# FPGA_E.net
KiCad netlist of a schematic drawn in Altium Designer
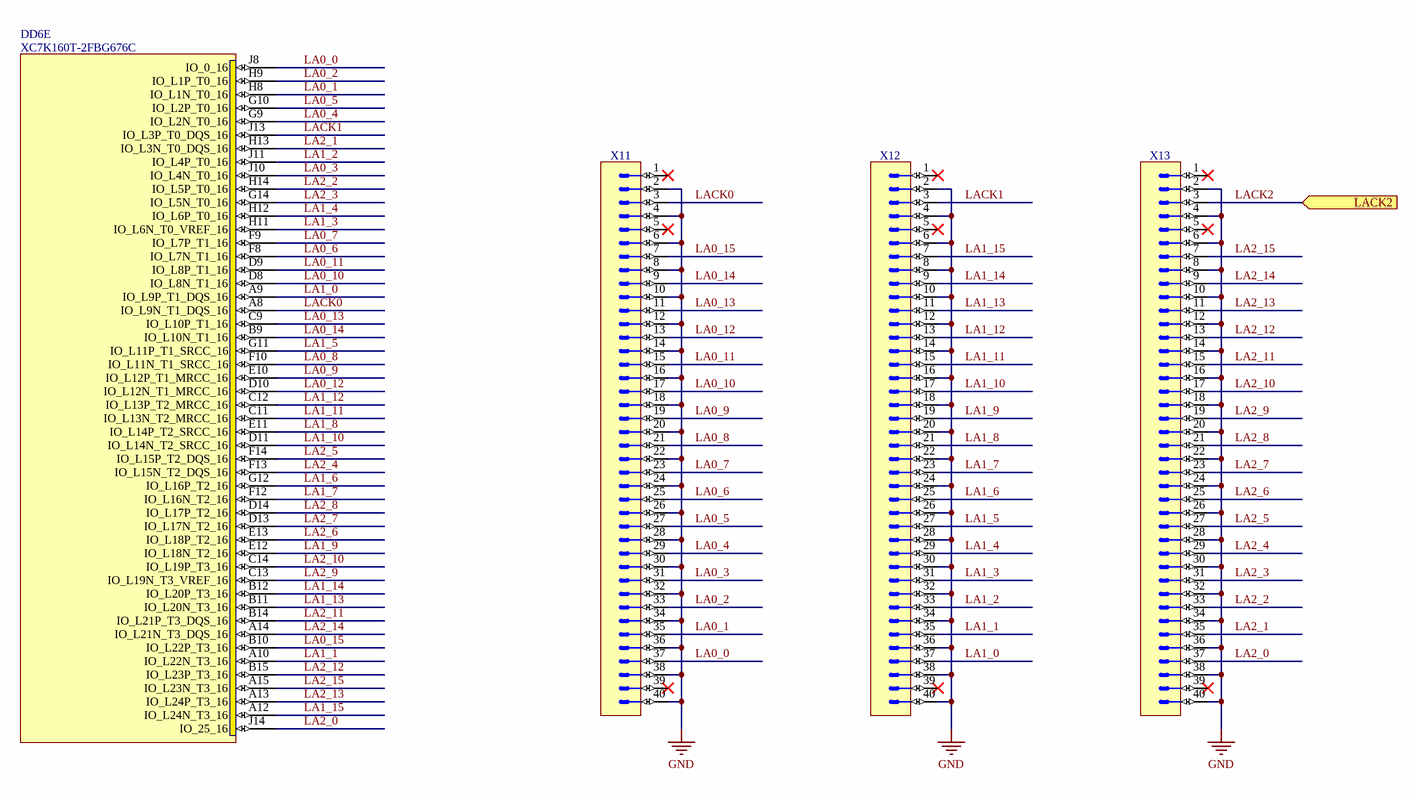
[diagram p0: FPGA_E.SchDoc]

(export (version "E")
  (design (tool "Eeschema 10.0.6"))
  (components
    (comp (ref "DD6")
      (value "XC7K160T-2FBG676C")
      (footprint "BGA676C100P26X26_2700X2700X254")
      (description "KINTEX-7, FPGA, 676-Ball BGA, Pb-Free")
      (fields (field (name "MANUFACTURER") "XILINX") (field (name "AUTHOR") "CERN DEM BC"))
      (libsource (lib "ICs And Semiconductors") (part "XC7K160T-xFBG676"))
    )
    (comp (ref "X11")
      (value "~")
      (footprint "CONNFLY_DS1013-40SSIB1-B-0")
      (description "Connector 40 Male")
      (fields
        (field (name "PART NUMBER") "CONNFLY_DS1013-40SSIB1-B-0")
        (field (name "MANUFACTURER") "CONNFLY")
        (field (name "AUTHOR") "CERN DEM HF")
      )
      (libsource (lib "Connectors") (part "Connector 40 Male"))
    )
    (comp (ref "X12")
      (value "~")
      (footprint "CONNFLY_DS1013-40SSIB1-B-0")
      (description "Connector 40 Male")
      (fields
        (field (name "PART NUMBER") "CONNFLY_DS1013-40SSIB1-B-0")
        (field (name "MANUFACTURER") "CONNFLY")
        (field (name "AUTHOR") "CERN DEM HF")
      )
      (libsource (lib "Connectors") (part "Connector 40 Male"))
    )
    (comp (ref "X13")
      (value "~")
      (footprint "CONNFLY_DS1013-40SSIB1-B-0")
      (description "Connector 40 Male")
      (fields
        (field (name "PART NUMBER") "CONNFLY_DS1013-40SSIB1-B-0")
        (field (name "MANUFACTURER") "CONNFLY")
        (field (name "AUTHOR") "CERN DEM HF")
      )
      (libsource (lib "Connectors") (part "Connector 40 Male"))
    )
  )
  (nets
    (net (code "1") (name "/LA0_0") (class "Default")
      (node (ref "DD6") (pin "J8") (pinfunction "IO_0_16_J8") (pintype "bidirectional"))
      (node (ref "X11") (pin "37") (pinfunction "37_37") (pintype "bidirectional"))
    )
    (net (code "2") (name "/LA0_1") (class "Default")
      (node (ref "DD6") (pin "H8") (pinfunction "IO_L1N_T0_16_H8") (pintype "bidirectional"))
      (node (ref "X11") (pin "35") (pinfunction "35_35") (pintype "bidirectional"))
    )
    (net (code "3") (name "/LA0_2") (class "Default")
      (node (ref "DD6") (pin "H9") (pinfunction "IO_L1P_T0_16_H9") (pintype "bidirectional"))
      (node (ref "X11") (pin "33") (pinfunction "33_33") (pintype "bidirectional"))
    )
    (net (code "4") (name "/LA0_3") (class "Default")
      (node (ref "DD6") (pin "J10") (pinfunction "IO_L4N_T0_16_J10") (pintype "bidirectional"))
      (node (ref "X11") (pin "31") (pinfunction "31_31") (pintype "bidirectional"))
    )
    (net (code "5") (name "/LA0_4") (class "Default")
      (node (ref "DD6") (pin "G9") (pinfunction "IO_L2N_T0_16_G9") (pintype "bidirectional"))
      (node (ref "X11") (pin "29") (pinfunction "29_29") (pintype "bidirectional"))
    )
    (net (code "6") (name "/LA0_5") (class "Default")
      (node (ref "DD6") (pin "G10") (pinfunction "IO_L2P_T0_16_G10") (pintype "bidirectional"))
      (node (ref "X11") (pin "27") (pinfunction "27_27") (pintype "bidirectional"))
    )
    (net (code "7") (name "/LA0_6") (class "Default")
      (node (ref "DD6") (pin "F8") (pinfunction "IO_L7N_T1_16_F8") (pintype "bidirectional"))
      (node (ref "X11") (pin "25") (pinfunction "25_25") (pintype "bidirectional"))
    )
    (net (code "8") (name "/LA0_7") (class "Default")
      (node (ref "DD6") (pin "F9") (pinfunction "IO_L7P_T1_16_F9") (pintype "bidirectional"))
      (node (ref "X11") (pin "23") (pinfunction "23_23") (pintype "bidirectional"))
    )
    (net (code "9") (name "/LA0_8") (class "Default")
      (node (ref "DD6") (pin "F10") (pinfunction "IO_L11N_T1_SRCC_16_F10") (pintype "bidirectional"))
      (node (ref "X11") (pin "21") (pinfunction "21_21") (pintype "bidirectional"))
    )
    (net (code "10") (name "/LA0_9") (class "Default")
      (node (ref "DD6") (pin "E10") (pinfunction "IO_L12P_T1_MRCC_16_E10") (pintype "bidirectional"))
      (node (ref "X11") (pin "19") (pinfunction "19_19") (pintype "bidirectional"))
    )
    (net (code "11") (name "/LA0_10") (class "Default")
      (node (ref "DD6") (pin "D8") (pinfunction "IO_L8N_T1_16_D8") (pintype "bidirectional"))
      (node (ref "X11") (pin "17") (pinfunction "17_17") (pintype "bidirectional"))
    )
    (net (code "12") (name "/LA0_11") (class "Default")
      (node (ref "DD6") (pin "D9") (pinfunction "IO_L8P_T1_16_D9") (pintype "bidirectional"))
      (node (ref "X11") (pin "15") (pinfunction "15_15") (pintype "bidirectional"))
    )
    (net (code "13") (name "/LA0_12") (class "Default")
      (node (ref "DD6") (pin "D10") (pinfunction "IO_L12N_T1_MRCC_16_D10") (pintype "bidirectional"))
      (node (ref "X11") (pin "13") (pinfunction "13_13") (pintype "bidirectional"))
    )
    (net (code "14") (name "/LA0_13") (class "Default")
      (node (ref "DD6") (pin "C9") (pinfunction "IO_L10P_T1_16_C9") (pintype "bidirectional"))
      (node (ref "X11") (pin "11") (pinfunction "11_11") (pintype "bidirectional"))
    )
    (net (code "15") (name "/LA0_14") (class "Default")
      (node (ref "DD6") (pin "B9") (pinfunction "IO_L10N_T1_16_B9") (pintype "bidirectional"))
      (node (ref "X11") (pin "9") (pinfunction "9_9") (pintype "bidirectional"))
    )
    (net (code "16") (name "/LA0_15") (class "Default")
      (node (ref "DD6") (pin "B10") (pinfunction "IO_L22P_T3_16_B10") (pintype "bidirectional"))
      (node (ref "X11") (pin "7") (pinfunction "7_7") (pintype "bidirectional"))
    )
    (net (code "17") (name "/LA1_0") (class "Default")
      (node (ref "DD6") (pin "A9") (pinfunction "IO_L9P_T1_DQS_16_A9") (pintype "bidirectional"))
      (node (ref "X12") (pin "37") (pinfunction "37_37") (pintype "bidirectional"))
    )
    (net (code "18") (name "/LA1_1") (class "Default")
      (node (ref "DD6") (pin "A10") (pinfunction "IO_L22N_T3_16_A10") (pintype "bidirectional"))
      (node (ref "X12") (pin "35") (pinfunction "35_35") (pintype "bidirectional"))
    )
    (net (code "19") (name "/LA1_2") (class "Default")
      (node (ref "DD6") (pin "J11") (pinfunction "IO_L4P_T0_16_J11") (pintype "bidirectional"))
      (node (ref "X12") (pin "33") (pinfunction "33_33") (pintype "bidirectional"))
    )
    (net (code "20") (name "/LA1_3") (class "Default")
      (node (ref "DD6") (pin "H11") (pinfunction "IO_L6N_T0_VREF_16_H11") (pintype "bidirectional"))
      (node (ref "X12") (pin "31") (pinfunction "31_31") (pintype "bidirectional"))
    )
    (net (code "21") (name "/LA1_4") (class "Default")
      (node (ref "DD6") (pin "H12") (pinfunction "IO_L6P_T0_16_H12") (pintype "bidirectional"))
      (node (ref "X12") (pin "29") (pinfunction "29_29") (pintype "bidirectional"))
    )
    (net (code "22") (name "/LA1_5") (class "Default")
      (node (ref "DD6") (pin "G11") (pinfunction "IO_L11P_T1_SRCC_16_G11") (pintype "bidirectional"))
      (node (ref "X12") (pin "27") (pinfunction "27_27") (pintype "bidirectional"))
    )
    (net (code "23") (name "/LA1_6") (class "Default")
      (node (ref "DD6") (pin "G12") (pinfunction "IO_L16P_T2_16_G12") (pintype "bidirectional"))
      (node (ref "X12") (pin "25") (pinfunction "25_25") (pintype "bidirectional"))
    )
    (net (code "24") (name "/LA1_7") (class "Default")
      (node (ref "DD6") (pin "F12") (pinfunction "IO_L16N_T2_16_F12") (pintype "bidirectional"))
      (node (ref "X12") (pin "23") (pinfunction "23_23") (pintype "bidirectional"))
    )
    (net (code "25") (name "/LA1_8") (class "Default")
      (node (ref "DD6") (pin "E11") (pinfunction "IO_L14P_T2_SRCC_16_E11") (pintype "bidirectional"))
      (node (ref "X12") (pin "21") (pinfunction "21_21") (pintype "bidirectional"))
    )
    (net (code "26") (name "/LA1_9") (class "Default")
      (node (ref "DD6") (pin "E12") (pinfunction "IO_L18N_T2_16_E12") (pintype "bidirectional"))
      (node (ref "X12") (pin "19") (pinfunction "19_19") (pintype "bidirectional"))
    )
    (net (code "27") (name "/LA1_10") (class "Default")
      (node (ref "DD6") (pin "D11") (pinfunction "IO_L14N_T2_SRCC_16_D11") (pintype "bidirectional"))
      (node (ref "X12") (pin "17") (pinfunction "17_17") (pintype "bidirectional"))
    )
    (net (code "28") (name "/LA1_11") (class "Default")
      (node (ref "DD6") (pin "C11") (pinfunction "IO_L13N_T2_MRCC_16_C11") (pintype "bidirectional"))
      (node (ref "X12") (pin "15") (pinfunction "15_15") (pintype "bidirectional"))
    )
    (net (code "29") (name "/LA1_12") (class "Default")
      (node (ref "DD6") (pin "C12") (pinfunction "IO_L13P_T2_MRCC_16_C12") (pintype "bidirectional"))
      (node (ref "X12") (pin "13") (pinfunction "13_13") (pintype "bidirectional"))
    )
    (net (code "30") (name "/LA1_13") (class "Default")
      (node (ref "DD6") (pin "B11") (pinfunction "IO_L20N_T3_16_B11") (pintype "bidirectional"))
      (node (ref "X12") (pin "11") (pinfunction "11_11") (pintype "bidirectional"))
    )
    (net (code "31") (name "/LA1_14") (class "Default")
      (node (ref "DD6") (pin "B12") (pinfunction "IO_L20P_T3_16_B12") (pintype "bidirectional"))
      (node (ref "X12") (pin "9") (pinfunction "9_9") (pintype "bidirectional"))
    )
    (net (code "32") (name "/LA1_15") (class "Default")
      (node (ref "DD6") (pin "A12") (pinfunction "IO_L24N_T3_16_A12") (pintype "bidirectional"))
      (node (ref "X12") (pin "7") (pinfunction "7_7") (pintype "bidirectional"))
    )
    (net (code "33") (name "/LA2_0") (class "Default")
      (node (ref "DD6") (pin "J14") (pinfunction "IO_25_16_J14") (pintype "bidirectional"))
      (node (ref "X13") (pin "37") (pinfunction "37_37") (pintype "bidirectional"))
    )
    (net (code "34") (name "/LA2_1") (class "Default")
      (node (ref "DD6") (pin "H13") (pinfunction "IO_L3N_T0_DQS_16_H13") (pintype "bidirectional"))
      (node (ref "X13") (pin "35") (pinfunction "35_35") (pintype "bidirectional"))
    )
    (net (code "35") (name "/LA2_2") (class "Default")
      (node (ref "DD6") (pin "H14") (pinfunction "IO_L5P_T0_16_H14") (pintype "bidirectional"))
      (node (ref "X13") (pin "33") (pinfunction "33_33") (pintype "bidirectional"))
    )
    (net (code "36") (name "/LA2_3") (class "Default")
      (node (ref "DD6") (pin "G14") (pinfunction "IO_L5N_T0_16_G14") (pintype "bidirectional"))
      (node (ref "X13") (pin "31") (pinfunction "31_31") (pintype "bidirectional"))
    )
    (net (code "37") (name "/LA2_4") (class "Default")
      (node (ref "DD6") (pin "F13") (pinfunction "IO_L15N_T2_DQS_16_F13") (pintype "bidirectional"))
      (node (ref "X13") (pin "29") (pinfunction "29_29") (pintype "bidirectional"))
    )
    (net (code "38") (name "/LA2_5") (class "Default")
      (node (ref "DD6") (pin "F14") (pinfunction "IO_L15P_T2_DQS_16_F14") (pintype "bidirectional"))
      (node (ref "X13") (pin "27") (pinfunction "27_27") (pintype "bidirectional"))
    )
    (net (code "39") (name "/LA2_6") (class "Default")
      (node (ref "DD6") (pin "E13") (pinfunction "IO_L18P_T2_16_E13") (pintype "bidirectional"))
      (node (ref "X13") (pin "25") (pinfunction "25_25") (pintype "bidirectional"))
    )
    (net (code "40") (name "/LA2_7") (class "Default")
      (node (ref "DD6") (pin "D13") (pinfunction "IO_L17N_T2_16_D13") (pintype "bidirectional"))
      (node (ref "X13") (pin "23") (pinfunction "23_23") (pintype "bidirectional"))
    )
    (net (code "41") (name "/LA2_8") (class "Default")
      (node (ref "DD6") (pin "D14") (pinfunction "IO_L17P_T2_16_D14") (pintype "bidirectional"))
      (node (ref "X13") (pin "21") (pinfunction "21_21") (pintype "bidirectional"))
    )
    (net (code "42") (name "/LA2_9") (class "Default")
      (node (ref "DD6") (pin "C13") (pinfunction "IO_L19N_T3_VREF_16_C13") (pintype "bidirectional"))
      (node (ref "X13") (pin "19") (pinfunction "19_19") (pintype "bidirectional"))
    )
    (net (code "43") (name "/LA2_10") (class "Default")
      (node (ref "DD6") (pin "C14") (pinfunction "IO_L19P_T3_16_C14") (pintype "bidirectional"))
      (node (ref "X13") (pin "17") (pinfunction "17_17") (pintype "bidirectional"))
    )
    (net (code "44") (name "/LA2_11") (class "Default")
      (node (ref "DD6") (pin "B14") (pinfunction "IO_L21P_T3_DQS_16_B14") (pintype "bidirectional"))
      (node (ref "X13") (pin "15") (pinfunction "15_15") (pintype "bidirectional"))
    )
    (net (code "45") (name "/LA2_12") (class "Default")
      (node (ref "DD6") (pin "B15") (pinfunction "IO_L23P_T3_16_B15") (pintype "bidirectional"))
      (node (ref "X13") (pin "13") (pinfunction "13_13") (pintype "bidirectional"))
    )
    (net (code "46") (name "/LA2_13") (class "Default")
      (node (ref "DD6") (pin "A13") (pinfunction "IO_L24P_T3_16_A13") (pintype "bidirectional"))
      (node (ref "X13") (pin "11") (pinfunction "11_11") (pintype "bidirectional"))
    )
    (net (code "47") (name "/LA2_14") (class "Default")
      (node (ref "DD6") (pin "A14") (pinfunction "IO_L21N_T3_DQS_16_A14") (pintype "bidirectional"))
      (node (ref "X13") (pin "9") (pinfunction "9_9") (pintype "bidirectional"))
    )
    (net (code "48") (name "/LA2_15") (class "Default")
      (node (ref "DD6") (pin "A15") (pinfunction "IO_L23N_T3_16_A15") (pintype "bidirectional"))
      (node (ref "X13") (pin "7") (pinfunction "7_7") (pintype "bidirectional"))
    )
    (net (code "49") (name "/LACK0") (class "Default")
      (node (ref "DD6") (pin "A8") (pinfunction "IO_L9N_T1_DQS_16_A8") (pintype "bidirectional"))
      (node (ref "X11") (pin "3") (pinfunction "3_3") (pintype "bidirectional"))
    )
    (net (code "50") (name "/LACK1") (class "Default")
      (node (ref "DD6") (pin "J13") (pinfunction "IO_L3P_T0_DQS_16_J13") (pintype "bidirectional"))
      (node (ref "X12") (pin "3") (pinfunction "3_3") (pintype "bidirectional"))
    )
    (net (code "51") (name "/LACK2") (class "Default")
      (node (ref "X13") (pin "3") (pinfunction "3_3") (pintype "bidirectional"))
    )
    (net (code "52") (name "GND") (class "Default")
      (node (ref "X11") (pin "10") (pinfunction "10_10") (pintype "bidirectional"))
      (node (ref "X11") (pin "12") (pinfunction "12_12") (pintype "bidirectional"))
      (node (ref "X11") (pin "14") (pinfunction "14_14") (pintype "bidirectional"))
      (node (ref "X11") (pin "16") (pinfunction "16_16") (pintype "bidirectional"))
      (node (ref "X11") (pin "18") (pinfunction "18_18") (pintype "bidirectional"))
      (node (ref "X11") (pin "2") (pinfunction "2_2") (pintype "bidirectional"))
      (node (ref "X11") (pin "20") (pinfunction "20_20") (pintype "bidirectional"))
      (node (ref "X11") (pin "22") (pinfunction "22_22") (pintype "bidirectional"))
      (node (ref "X11") (pin "24") (pinfunction "24_24") (pintype "bidirectional"))
      (node (ref "X11") (pin "26") (pinfunction "26_26") (pintype "bidirectional"))
      (node (ref "X11") (pin "28") (pinfunction "28_28") (pintype "bidirectional"))
      (node (ref "X11") (pin "30") (pinfunction "30_30") (pintype "bidirectional"))
      (node (ref "X11") (pin "32") (pinfunction "32_32") (pintype "bidirectional"))
      (node (ref "X11") (pin "34") (pinfunction "34_34") (pintype "bidirectional"))
      (node (ref "X11") (pin "36") (pinfunction "36_36") (pintype "bidirectional"))
      (node (ref "X11") (pin "38") (pinfunction "38_38") (pintype "bidirectional"))
      (node (ref "X11") (pin "4") (pinfunction "4_4") (pintype "bidirectional"))
      (node (ref "X11") (pin "40") (pinfunction "40_40") (pintype "bidirectional"))
      (node (ref "X11") (pin "6") (pinfunction "6_6") (pintype "bidirectional"))
      (node (ref "X11") (pin "8") (pinfunction "8_8") (pintype "bidirectional"))
      (node (ref "X12") (pin "10") (pinfunction "10_10") (pintype "bidirectional"))
      (node (ref "X12") (pin "12") (pinfunction "12_12") (pintype "bidirectional"))
      (node (ref "X12") (pin "14") (pinfunction "14_14") (pintype "bidirectional"))
      (node (ref "X12") (pin "16") (pinfunction "16_16") (pintype "bidirectional"))
      (node (ref "X12") (pin "18") (pinfunction "18_18") (pintype "bidirectional"))
      (node (ref "X12") (pin "2") (pinfunction "2_2") (pintype "bidirectional"))
      (node (ref "X12") (pin "20") (pinfunction "20_20") (pintype "bidirectional"))
      (node (ref "X12") (pin "22") (pinfunction "22_22") (pintype "bidirectional"))
      (node (ref "X12") (pin "24") (pinfunction "24_24") (pintype "bidirectional"))
      (node (ref "X12") (pin "26") (pinfunction "26_26") (pintype "bidirectional"))
      (node (ref "X12") (pin "28") (pinfunction "28_28") (pintype "bidirectional"))
      (node (ref "X12") (pin "30") (pinfunction "30_30") (pintype "bidirectional"))
      (node (ref "X12") (pin "32") (pinfunction "32_32") (pintype "bidirectional"))
      (node (ref "X12") (pin "34") (pinfunction "34_34") (pintype "bidirectional"))
      (node (ref "X12") (pin "36") (pinfunction "36_36") (pintype "bidirectional"))
      (node (ref "X12") (pin "38") (pinfunction "38_38") (pintype "bidirectional"))
      (node (ref "X12") (pin "4") (pinfunction "4_4") (pintype "bidirectional"))
      (node (ref "X12") (pin "40") (pinfunction "40_40") (pintype "bidirectional"))
      (node (ref "X12") (pin "6") (pinfunction "6_6") (pintype "bidirectional"))
      (node (ref "X12") (pin "8") (pinfunction "8_8") (pintype "bidirectional"))
      (node (ref "X13") (pin "10") (pinfunction "10_10") (pintype "bidirectional"))
      (node (ref "X13") (pin "12") (pinfunction "12_12") (pintype "bidirectional"))
      (node (ref "X13") (pin "14") (pinfunction "14_14") (pintype "bidirectional"))
      (node (ref "X13") (pin "16") (pinfunction "16_16") (pintype "bidirectional"))
      (node (ref "X13") (pin "18") (pinfunction "18_18") (pintype "bidirectional"))
      (node (ref "X13") (pin "2") (pinfunction "2_2") (pintype "bidirectional"))
      (node (ref "X13") (pin "20") (pinfunction "20_20") (pintype "bidirectional"))
      (node (ref "X13") (pin "22") (pinfunction "22_22") (pintype "bidirectional"))
      (node (ref "X13") (pin "24") (pinfunction "24_24") (pintype "bidirectional"))
      (node (ref "X13") (pin "26") (pinfunction "26_26") (pintype "bidirectional"))
      (node (ref "X13") (pin "28") (pinfunction "28_28") (pintype "bidirectional"))
      (node (ref "X13") (pin "30") (pinfunction "30_30") (pintype "bidirectional"))
      (node (ref "X13") (pin "32") (pinfunction "32_32") (pintype "bidirectional"))
      (node (ref "X13") (pin "34") (pinfunction "34_34") (pintype "bidirectional"))
      (node (ref "X13") (pin "36") (pinfunction "36_36") (pintype "bidirectional"))
      (node (ref "X13") (pin "38") (pinfunction "38_38") (pintype "bidirectional"))
      (node (ref "X13") (pin "4") (pinfunction "4_4") (pintype "bidirectional"))
      (node (ref "X13") (pin "40") (pinfunction "40_40") (pintype "bidirectional"))
      (node (ref "X13") (pin "6") (pinfunction "6_6") (pintype "bidirectional"))
      (node (ref "X13") (pin "8") (pinfunction "8_8") (pintype "bidirectional"))
    )
    (net (code "53") (name "unconnected-(X11-Pad1)") (class "Default")
      (node (ref "X11") (pin "1") (pinfunction "1_1") (pintype "bidirectional+no_connect"))
    )
    (net (code "54") (name "unconnected-(X11-Pad5)") (class "Default")
      (node (ref "X11") (pin "5") (pinfunction "5_5") (pintype "bidirectional+no_connect"))
    )
    (net (code "55") (name "unconnected-(X11-Pad39)") (class "Default")
      (node (ref "X11") (pin "39") (pinfunction "39_39") (pintype "bidirectional+no_connect"))
    )
    (net (code "56") (name "unconnected-(X12-Pad1)") (class "Default")
      (node (ref "X12") (pin "1") (pinfunction "1_1") (pintype "bidirectional+no_connect"))
    )
    (net (code "57") (name "unconnected-(X12-Pad5)") (class "Default")
      (node (ref "X12") (pin "5") (pinfunction "5_5") (pintype "bidirectional+no_connect"))
    )
    (net (code "58") (name "unconnected-(X12-Pad39)") (class "Default")
      (node (ref "X12") (pin "39") (pinfunction "39_39") (pintype "bidirectional+no_connect"))
    )
    (net (code "59") (name "unconnected-(X13-Pad1)") (class "Default")
      (node (ref "X13") (pin "1") (pinfunction "1_1") (pintype "bidirectional+no_connect"))
    )
    (net (code "60") (name "unconnected-(X13-Pad5)") (class "Default")
      (node (ref "X13") (pin "5") (pinfunction "5_5") (pintype "bidirectional+no_connect"))
    )
    (net (code "61") (name "unconnected-(X13-Pad39)") (class "Default")
      (node (ref "X13") (pin "39") (pinfunction "39_39") (pintype "bidirectional+no_connect"))
    )
  )
)
